# display.net
KiCad netlist of a schematic drawn in EAGLE
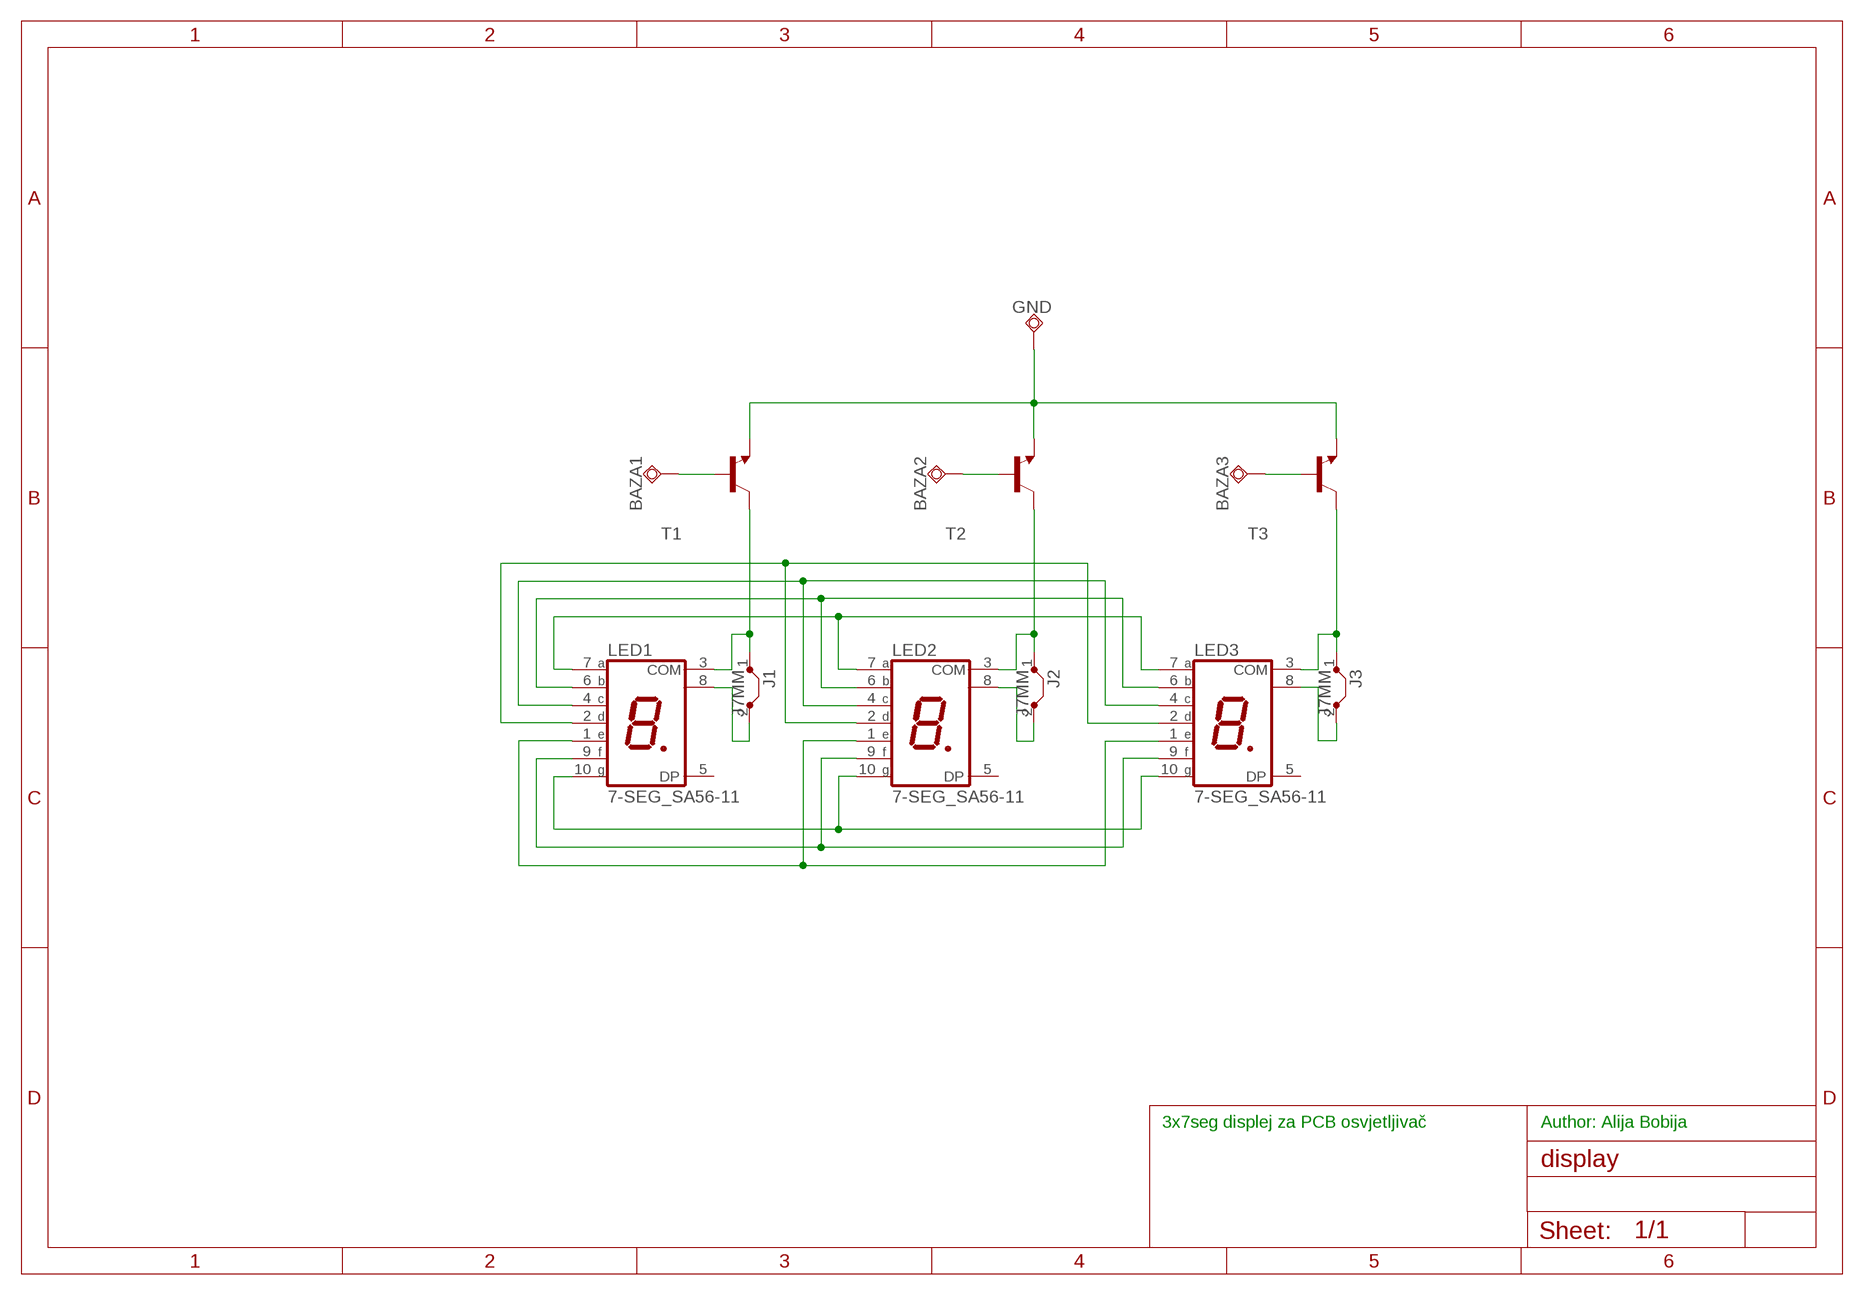
[diagram p0: schematic, sheet 1]

(export (version "E")
  (design (tool "Eeschema 10.0.6"))
  (components
    (comp (ref "BAZA1")
      (value "TPSQTP20SQ")
      (footprint "eagle-import:TP20SQ")
      (libsource (lib "eagle-import") (part "TPSQTP20SQ"))
    )
    (comp (ref "BAZA2")
      (value "TPSQTP20SQ")
      (footprint "eagle-import:TP20SQ")
      (libsource (lib "eagle-import") (part "TPSQTP20SQ"))
    )
    (comp (ref "BAZA3")
      (value "TPSQTP20SQ")
      (footprint "eagle-import:TP20SQ")
      (libsource (lib "eagle-import") (part "TPSQTP20SQ"))
    )
    (comp (ref "GND")
      (value "TPSQTP20SQ")
      (footprint "eagle-import:TP20SQ")
      (libsource (lib "eagle-import") (part "TPSQTP20SQ"))
    )
    (comp (ref "J1")
      (value "J7MM")
      (footprint "eagle-import:07")
      (libsource (lib "eagle-import") (part "J7MM"))
    )
    (comp (ref "J2")
      (value "J7MM")
      (footprint "eagle-import:07")
      (libsource (lib "eagle-import") (part "J7MM"))
    )
    (comp (ref "J3")
      (value "J7MM")
      (footprint "eagle-import:07")
      (libsource (lib "eagle-import") (part "J7MM"))
    )
    (comp (ref "LED1")
      (value "7-SEG_SA56-11")
      (footprint "eagle-import:SA56-11")
      (libsource (lib "eagle-import") (part "7-SEG_SA56-11"))
    )
    (comp (ref "LED2")
      (value "7-SEG_SA56-11")
      (footprint "eagle-import:SA56-11")
      (libsource (lib "eagle-import") (part "7-SEG_SA56-11"))
    )
    (comp (ref "LED3")
      (value "7-SEG_SA56-11")
      (footprint "eagle-import:SA56-11")
      (libsource (lib "eagle-import") (part "7-SEG_SA56-11"))
    )
    (comp (ref "T1")
      (value "-NPN-SOT23-EBC")
      (footprint "eagle-import:SOT23-EBC")
      (libsource (lib "eagle-import") (part "-NPN-SOT23-EBC"))
    )
    (comp (ref "T2")
      (value "-NPN-SOT23-EBC")
      (footprint "eagle-import:SOT23-EBC")
      (libsource (lib "eagle-import") (part "-NPN-SOT23-EBC"))
    )
    (comp (ref "T3")
      (value "-NPN-SOT23-EBC")
      (footprint "eagle-import:SOT23-EBC")
      (libsource (lib "eagle-import") (part "-NPN-SOT23-EBC"))
    )
  )
  (nets
    (net (code "1") (name "Net-(BAZA1-PadTP)") (class "Default")
      (node (ref "BAZA1") (pin "TP") (pinfunction "TP_TP") (pintype "input"))
      (node (ref "T1") (pin "B") (pinfunction "B_B") (pintype "passive"))
    )
    (net (code "2") (name "Net-(BAZA2-PadTP)") (class "Default")
      (node (ref "BAZA2") (pin "TP") (pinfunction "TP_TP") (pintype "input"))
      (node (ref "T2") (pin "B") (pinfunction "B_B") (pintype "passive"))
    )
    (net (code "3") (name "Net-(BAZA3-PadTP)") (class "Default")
      (node (ref "BAZA3") (pin "TP") (pinfunction "TP_TP") (pintype "input"))
      (node (ref "T3") (pin "B") (pinfunction "B_B") (pintype "passive"))
    )
    (net (code "4") (name "Net-(GND-PadTP)") (class "Default")
      (node (ref "GND") (pin "TP") (pinfunction "TP_TP") (pintype "input"))
      (node (ref "T1") (pin "E") (pinfunction "E_E") (pintype "passive"))
      (node (ref "T2") (pin "E") (pinfunction "E_E") (pintype "passive"))
      (node (ref "T3") (pin "E") (pinfunction "E_E") (pintype "passive"))
    )
    (net (code "5") (name "Net-(J1-Pad1)") (class "Default")
      (node (ref "J1") (pin "1") (pinfunction "1_1") (pintype "passive"))
      (node (ref "LED1") (pin "3") (pinfunction "COM_3") (pintype "passive"))
      (node (ref "T1") (pin "C") (pinfunction "C_C") (pintype "passive"))
    )
    (net (code "6") (name "Net-(J1-Pad2)") (class "Default")
      (node (ref "J1") (pin "2") (pinfunction "2_2") (pintype "passive"))
      (node (ref "LED1") (pin "8") (pinfunction "COM_8") (pintype "passive"))
    )
    (net (code "7") (name "Net-(J2-Pad1)") (class "Default")
      (node (ref "J2") (pin "1") (pinfunction "1_1") (pintype "passive"))
      (node (ref "LED2") (pin "3") (pinfunction "COM_3") (pintype "passive"))
      (node (ref "T2") (pin "C") (pinfunction "C_C") (pintype "passive"))
    )
    (net (code "8") (name "Net-(J2-Pad2)") (class "Default")
      (node (ref "J2") (pin "2") (pinfunction "2_2") (pintype "passive"))
      (node (ref "LED2") (pin "8") (pinfunction "COM_8") (pintype "passive"))
    )
    (net (code "9") (name "Net-(J3-Pad1)") (class "Default")
      (node (ref "J3") (pin "1") (pinfunction "1_1") (pintype "passive"))
      (node (ref "LED3") (pin "3") (pinfunction "COM_3") (pintype "passive"))
      (node (ref "T3") (pin "C") (pinfunction "C_C") (pintype "passive"))
    )
    (net (code "10") (name "Net-(J3-Pad2)") (class "Default")
      (node (ref "J3") (pin "2") (pinfunction "2_2") (pintype "passive"))
      (node (ref "LED3") (pin "8") (pinfunction "COM_8") (pintype "passive"))
    )
    (net (code "11") (name "Net-(LED1-A)") (class "Default")
      (node (ref "LED1") (pin "7") (pinfunction "A_7") (pintype "passive"))
      (node (ref "LED2") (pin "7") (pinfunction "A_7") (pintype "passive"))
      (node (ref "LED3") (pin "7") (pinfunction "A_7") (pintype "passive"))
    )
    (net (code "12") (name "Net-(LED1-B)") (class "Default")
      (node (ref "LED1") (pin "6") (pinfunction "B_6") (pintype "passive"))
      (node (ref "LED2") (pin "6") (pinfunction "B_6") (pintype "passive"))
      (node (ref "LED3") (pin "6") (pinfunction "B_6") (pintype "passive"))
    )
    (net (code "13") (name "Net-(LED1-C)") (class "Default")
      (node (ref "LED1") (pin "4") (pinfunction "C_4") (pintype "passive"))
      (node (ref "LED2") (pin "4") (pinfunction "C_4") (pintype "passive"))
      (node (ref "LED3") (pin "4") (pinfunction "C_4") (pintype "passive"))
    )
    (net (code "14") (name "Net-(LED1-D)") (class "Default")
      (node (ref "LED1") (pin "2") (pinfunction "D_2") (pintype "passive"))
      (node (ref "LED2") (pin "2") (pinfunction "D_2") (pintype "passive"))
      (node (ref "LED3") (pin "2") (pinfunction "D_2") (pintype "passive"))
    )
    (net (code "15") (name "Net-(LED1-E)") (class "Default")
      (node (ref "LED1") (pin "1") (pinfunction "E_1") (pintype "passive"))
      (node (ref "LED2") (pin "1") (pinfunction "E_1") (pintype "passive"))
      (node (ref "LED3") (pin "1") (pinfunction "E_1") (pintype "passive"))
    )
    (net (code "16") (name "Net-(LED1-F)") (class "Default")
      (node (ref "LED1") (pin "9") (pinfunction "F_9") (pintype "passive"))
      (node (ref "LED2") (pin "9") (pinfunction "F_9") (pintype "passive"))
      (node (ref "LED3") (pin "9") (pinfunction "F_9") (pintype "passive"))
    )
    (net (code "17") (name "Net-(LED1-G)") (class "Default")
      (node (ref "LED1") (pin "10") (pinfunction "G_10") (pintype "passive"))
      (node (ref "LED2") (pin "10") (pinfunction "G_10") (pintype "passive"))
      (node (ref "LED3") (pin "10") (pinfunction "G_10") (pintype "passive"))
    )
    (net (code "18") (name "unconnected-(LED1-DP-Pad5)") (class "Default")
      (node (ref "LED1") (pin "5") (pinfunction "DP_5") (pintype "passive"))
    )
    (net (code "19") (name "unconnected-(LED2-DP-Pad5)") (class "Default")
      (node (ref "LED2") (pin "5") (pinfunction "DP_5") (pintype "passive"))
    )
    (net (code "20") (name "unconnected-(LED3-DP-Pad5)") (class "Default")
      (node (ref "LED3") (pin "5") (pinfunction "DP_5") (pintype "passive"))
    )
  )
)
